# OnofreWireShield.net
KiCad netlist of a schematic drawn in EAGLE
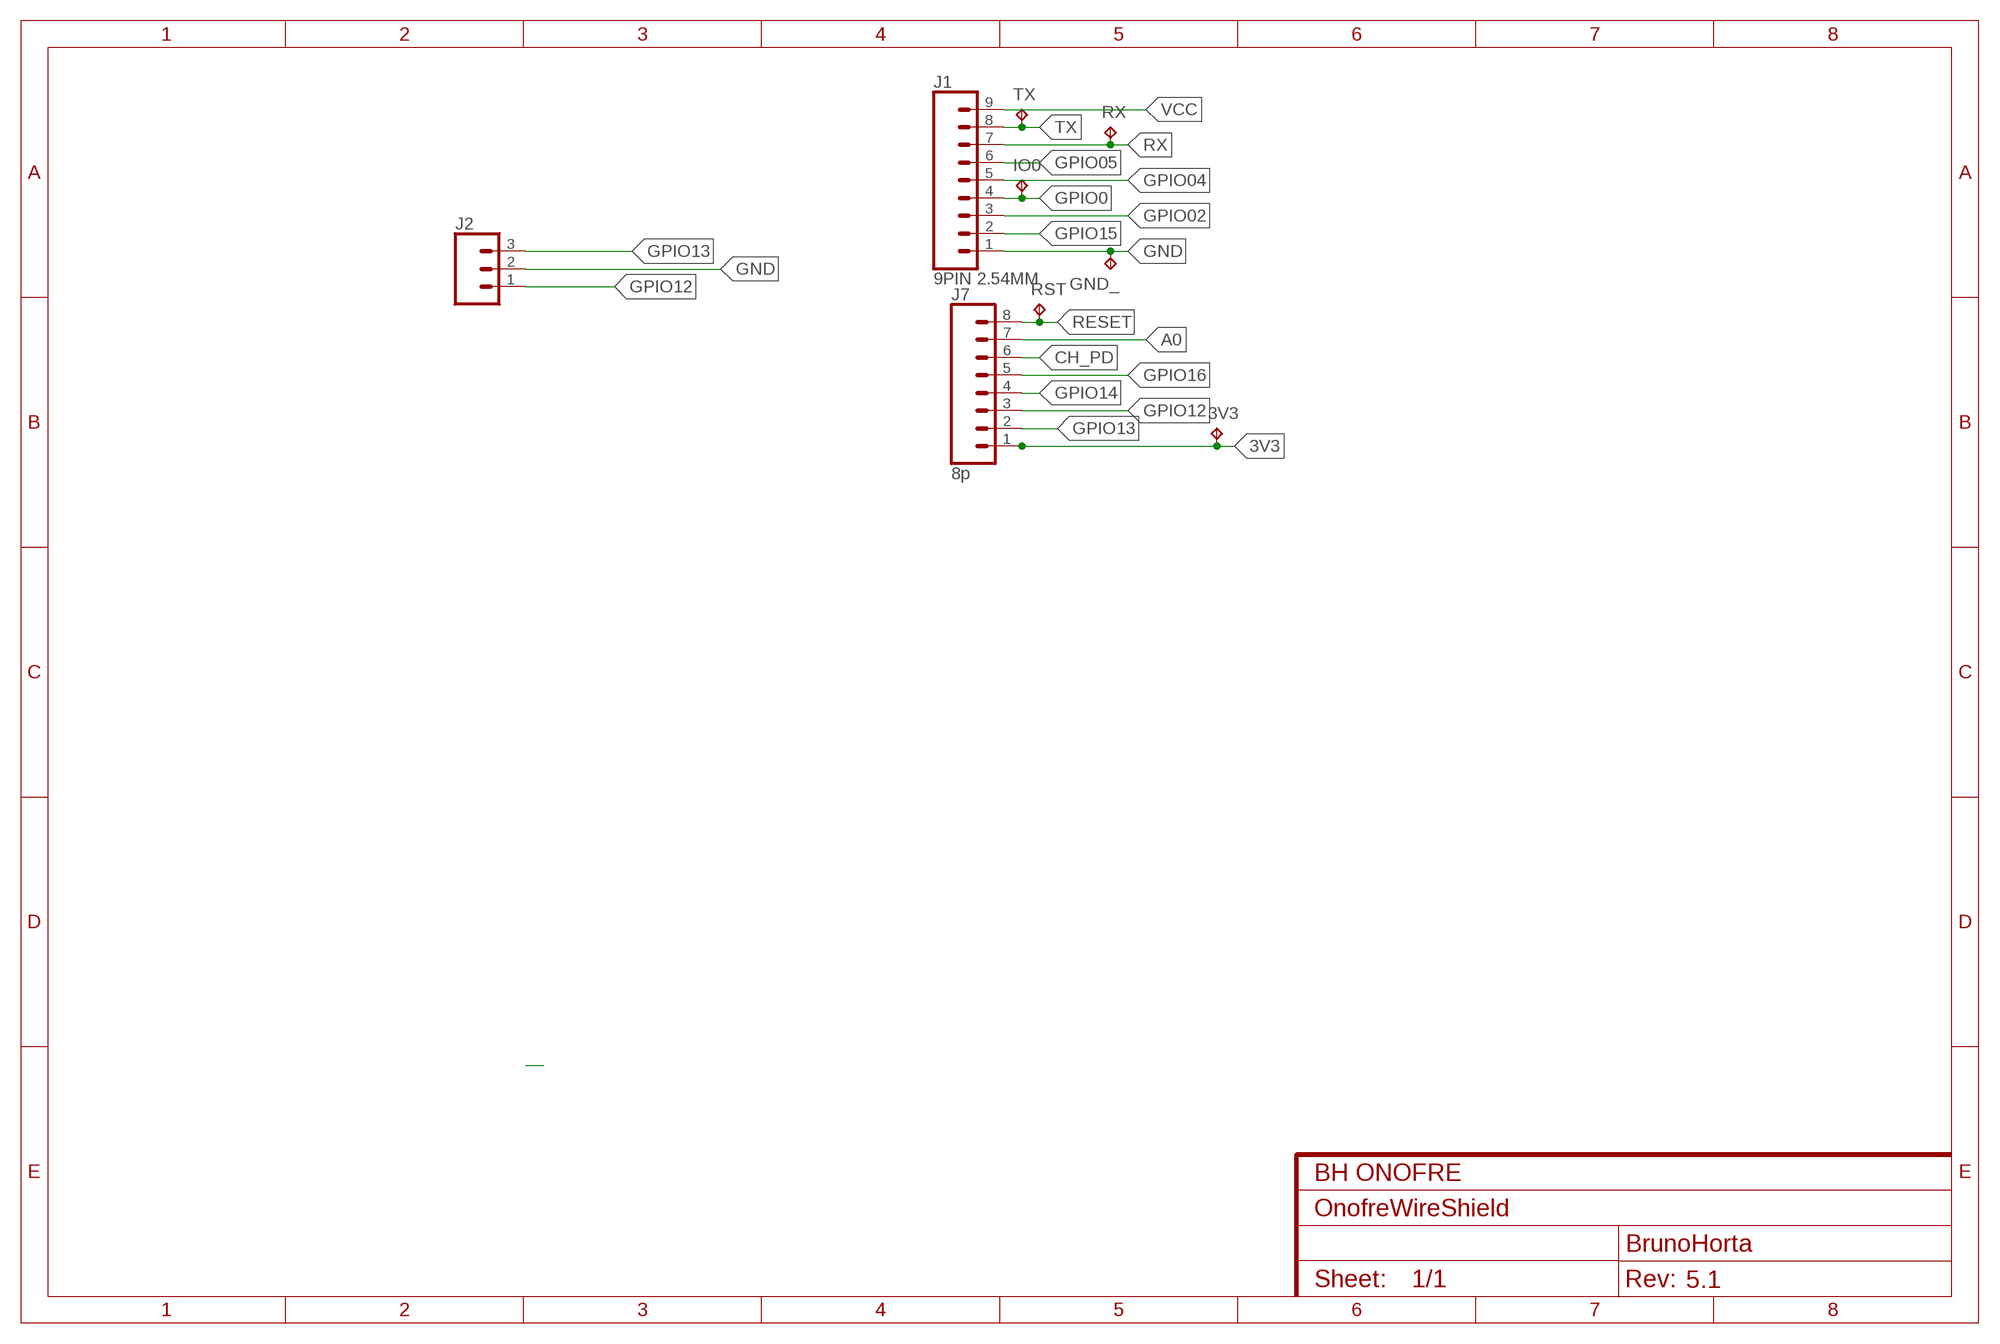
[diagram p0: schematic, sheet 1]

(export (version "E")
  (design (tool "Eeschema 10.0.6"))
  (components
    (comp (ref "3V3")
      (value "TPB1,27")
      (footprint "eagle-import:B1,27")
      (libsource (lib "eagle-import") (part "TPB1,27"))
    )
    (comp (ref "GND_")
      (value "TPB1,27")
      (footprint "eagle-import:B1,27")
      (libsource (lib "eagle-import") (part "TPB1,27"))
    )
    (comp (ref "IO0")
      (value "TPB1,27")
      (footprint "eagle-import:B1,27")
      (libsource (lib "eagle-import") (part "TPB1,27"))
    )
    (comp (ref "J1")
      (value "9PIN 2.54MM")
      (footprint "eagle-import:1X09")
      (libsource (lib "eagle-import") (part "CONN_09"))
    )
    (comp (ref "J2")
      (value "CONN_03")
      (footprint "eagle-import:1X03")
      (libsource (lib "eagle-import") (part "CONN_03"))
    )
    (comp (ref "J7")
      (value "8p")
      (footprint "eagle-import:1X08")
      (libsource (lib "eagle-import") (part "CONN_08{dblquote}"))
    )
    (comp (ref "RST")
      (value "TPB1,27")
      (footprint "eagle-import:B1,27")
      (libsource (lib "eagle-import") (part "TPB1,27"))
    )
    (comp (ref "RX")
      (value "TPB1,27")
      (footprint "eagle-import:B1,27")
      (libsource (lib "eagle-import") (part "TPB1,27"))
    )
    (comp (ref "TX")
      (value "TPB1,27")
      (footprint "eagle-import:B1,27")
      (libsource (lib "eagle-import") (part "TPB1,27"))
    )
  )
  (nets
    (net (code "1") (name "3V3") (class "Default")
      (node (ref "3V3") (pin "TP") (pinfunction "TP_TP") (pintype "input"))
      (node (ref "J7") (pin "1") (pinfunction "1_1") (pintype "passive"))
    )
    (net (code "2") (name "A0") (class "Default")
      (node (ref "J7") (pin "7") (pinfunction "7_7") (pintype "passive"))
    )
    (net (code "3") (name "CH_PD") (class "Default")
      (node (ref "J7") (pin "6") (pinfunction "6_6") (pintype "passive"))
    )
    (net (code "4") (name "GND") (class "Default")
      (node (ref "GND_") (pin "TP") (pinfunction "TP_TP") (pintype "input"))
      (node (ref "J1") (pin "1") (pinfunction "1_1") (pintype "passive"))
      (node (ref "J2") (pin "2") (pinfunction "2_2") (pintype "passive"))
    )
    (net (code "5") (name "GPIO0") (class "Default")
      (node (ref "IO0") (pin "TP") (pinfunction "TP_TP") (pintype "input"))
      (node (ref "J1") (pin "4") (pinfunction "4_4") (pintype "passive"))
    )
    (net (code "6") (name "GPIO02") (class "Default")
      (node (ref "J1") (pin "3") (pinfunction "3_3") (pintype "passive"))
    )
    (net (code "7") (name "GPIO04") (class "Default")
      (node (ref "J1") (pin "5") (pinfunction "5_5") (pintype "passive"))
    )
    (net (code "8") (name "GPIO05") (class "Default")
      (node (ref "J1") (pin "6") (pinfunction "6_6") (pintype "passive"))
    )
    (net (code "9") (name "GPIO12") (class "Default")
      (node (ref "J2") (pin "1") (pinfunction "1_1") (pintype "passive"))
      (node (ref "J7") (pin "3") (pinfunction "3_3") (pintype "passive"))
    )
    (net (code "10") (name "GPIO13") (class "Default")
      (node (ref "J2") (pin "3") (pinfunction "3_3") (pintype "passive"))
      (node (ref "J7") (pin "2") (pinfunction "2_2") (pintype "passive"))
    )
    (net (code "11") (name "GPIO14") (class "Default")
      (node (ref "J7") (pin "4") (pinfunction "4_4") (pintype "passive"))
    )
    (net (code "12") (name "GPIO15") (class "Default")
      (node (ref "J1") (pin "2") (pinfunction "2_2") (pintype "passive"))
    )
    (net (code "13") (name "GPIO16") (class "Default")
      (node (ref "J7") (pin "5") (pinfunction "5_5") (pintype "passive"))
    )
    (net (code "14") (name "RESET") (class "Default")
      (node (ref "J7") (pin "8") (pinfunction "8_8") (pintype "passive"))
      (node (ref "RST") (pin "TP") (pinfunction "TP_TP") (pintype "input"))
    )
    (net (code "15") (name "RX") (class "Default")
      (node (ref "J1") (pin "7") (pinfunction "7_7") (pintype "passive"))
      (node (ref "RX") (pin "TP") (pinfunction "TP_TP") (pintype "input"))
    )
    (net (code "16") (name "TX") (class "Default")
      (node (ref "J1") (pin "8") (pinfunction "8_8") (pintype "passive"))
      (node (ref "TX") (pin "TP") (pinfunction "TP_TP") (pintype "input"))
    )
    (net (code "17") (name "VCC") (class "Default")
      (node (ref "J1") (pin "9") (pinfunction "9_9") (pintype "passive"))
    )
  )
)
